# Thermistor.net
KiCad netlist of a schematic drawn in Altium Designer
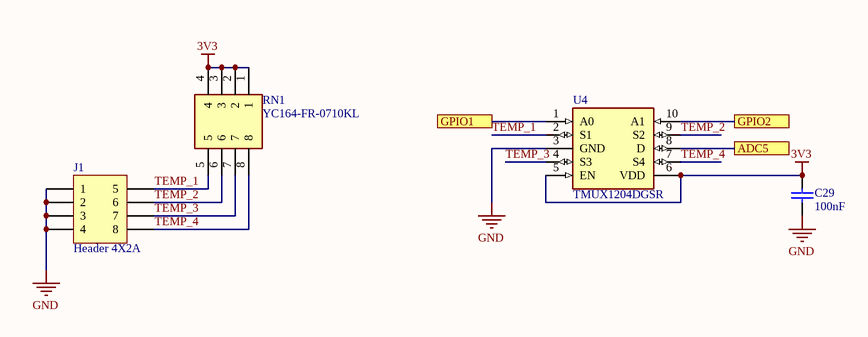
[diagram p0: Thermistor.SchDoc]

(export (version "E")
  (design (tool "Eeschema 10.0.6"))
  (components
    (comp (ref "C29")
      (value "100nF")
      (footprint "C0805")
      (description "C0805C104K8RACTU. 0.1µF ±10% 10V Ceramic Capacitor X7R 0805 (2012 Metric)")
      (fields (field (name "Comment") "10V") (field (name "PUBLISHER") "Altium Limited"))
      (libsource (lib "Miscellaneous Devices") (part "Cap"))
    )
    (comp (ref "J1")
      (value "Header 4X2A")
      (footprint "HDR2X4_CEN")
      (description "Header, 4-Pin, Dual row")
      (fields (field (name "PUBLISHER") "Altium Limited"))
      (libsource (lib "Miscellaneous Connectors") (part "Header 4X2A"))
    )
    (comp (ref "RN1")
      (value "YC164-FR-0710KL")
      (footprint "Motor Controller:YC164JR07220RL")
      (description "Resistor Network")
      (fields (field (name "MOUSER PART NUMBER") "603-YC164-FR-0710KL"))
      (libsource (lib "Motor Controller") (part "YC164-FR-0710KL"))
    )
    (comp (ref "U4")
      (value "TMUX1204DGSR")
      (footprint "Motor Controller:SOP50P490X110-10N")
      (description "Integrated Circuit")
      (fields (field (name "MOUSER PART NUMBER") "595-TMUX1204DGSR"))
      (libsource (lib "Motor Controller") (part "TMUX1204DGSR"))
    )
  )
  (nets
    (net (code "1") (name "/ADC5") (class "Default")
      (node (ref "U4") (pin "8") (pinfunction "D_8") (pintype "bidirectional"))
    )
    (net (code "2") (name "/GPIO1") (class "Default")
      (node (ref "U4") (pin "1") (pinfunction "A0_1") (pintype "input"))
    )
    (net (code "3") (name "/GPIO2") (class "Default")
      (node (ref "U4") (pin "10") (pinfunction "A1_10") (pintype "input"))
    )
    (net (code "4") (name "/TEMP_1") (class "Default")
      (node (ref "J1") (pin "5") (pinfunction "5_5") (pintype "passive"))
      (node (ref "RN1") (pin "5") (pinfunction "5_5") (pintype "passive"))
      (node (ref "U4") (pin "2") (pinfunction "S1_2") (pintype "bidirectional"))
    )
    (net (code "5") (name "/TEMP_2") (class "Default")
      (node (ref "J1") (pin "6") (pinfunction "6_6") (pintype "passive"))
      (node (ref "RN1") (pin "6") (pinfunction "6_6") (pintype "passive"))
      (node (ref "U4") (pin "9") (pinfunction "S2_9") (pintype "bidirectional"))
    )
    (net (code "6") (name "/TEMP_3") (class "Default")
      (node (ref "J1") (pin "7") (pinfunction "7_7") (pintype "passive"))
      (node (ref "RN1") (pin "7") (pinfunction "7_7") (pintype "passive"))
      (node (ref "U4") (pin "4") (pinfunction "S3_4") (pintype "bidirectional"))
    )
    (net (code "7") (name "/TEMP_4") (class "Default")
      (node (ref "J1") (pin "8") (pinfunction "8_8") (pintype "passive"))
      (node (ref "RN1") (pin "8") (pinfunction "8_8") (pintype "passive"))
      (node (ref "U4") (pin "7") (pinfunction "S4_7") (pintype "bidirectional"))
    )
    (net (code "8") (name "3V3") (class "Default")
      (node (ref "C29") (pin "1") (pinfunction "1_1") (pintype "passive"))
      (node (ref "RN1") (pin "1") (pinfunction "1_1") (pintype "passive"))
      (node (ref "RN1") (pin "2") (pinfunction "2_2") (pintype "passive"))
      (node (ref "RN1") (pin "3") (pinfunction "3_3") (pintype "passive"))
      (node (ref "RN1") (pin "4") (pinfunction "4_4") (pintype "passive"))
      (node (ref "U4") (pin "5") (pinfunction "EN_5") (pintype "input"))
      (node (ref "U4") (pin "6") (pinfunction "VDD_6") (pintype "power_in"))
    )
    (net (code "9") (name "GND") (class "Default")
      (node (ref "C29") (pin "2") (pinfunction "2_2") (pintype "passive"))
      (node (ref "J1") (pin "1") (pinfunction "1_1") (pintype "passive"))
      (node (ref "J1") (pin "2") (pinfunction "2_2") (pintype "passive"))
      (node (ref "J1") (pin "3") (pinfunction "3_3") (pintype "passive"))
      (node (ref "J1") (pin "4") (pinfunction "4_4") (pintype "passive"))
      (node (ref "U4") (pin "3") (pinfunction "GND_3") (pintype "power_in"))
    )
  )
)
